# debug-header-feather.net
KiCad netlist of a schematic drawn in EAGLE
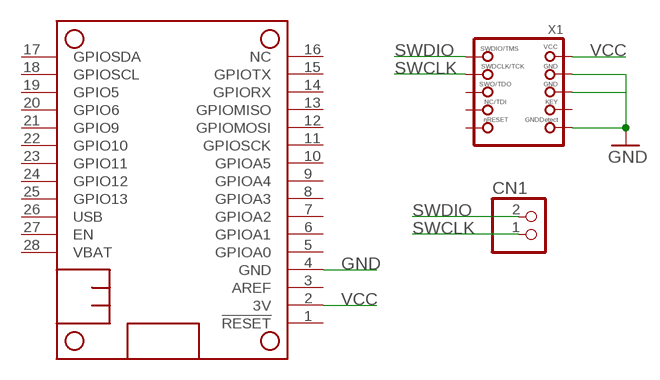
[diagram p0: schematic, sheet 1]

(export (version "E")
  (design (tool "Eeschema 10.0.6"))
  (components
    (comp (ref "CN1")
      (value "JST_2PIN-SMT-RA")
      (footprint "eagle-import:JST-PH-2-SMT-RA")
      (libsource (lib "eagle-import") (part "JST_2PIN-SMT-RA"))
    )
    (comp (ref "MS1")
      (value "FEATHERWING")
      (footprint "eagle-import:FEATHERWING")
      (libsource (lib "eagle-import") (part "FEATHERWING"))
    )
    (comp (ref "X1")
      (value "JTAG-CORTEX")
      (footprint "eagle-import:2X05_1.27MM_SMT")
      (libsource (lib "eagle-import") (part "JTAG-CORTEX"))
    )
  )
  (nets
    (net (code "1") (name "/SWCLK") (class "Default")
      (node (ref "CN1") (pin "1") (pinfunction "2_1") (pintype "passive"))
      (node (ref "X1") (pin "4") (pinfunction "SWDCLK_4") (pintype "bidirectional"))
    )
    (net (code "2") (name "/SWDIO") (class "Default")
      (node (ref "CN1") (pin "2") (pinfunction "1_2") (pintype "passive"))
      (node (ref "X1") (pin "2") (pinfunction "SWDIO_2") (pintype "bidirectional"))
    )
    (net (code "3") (name "/USB") (class "Default")
      (node (ref "MS1") (pin "26") (pinfunction "USB_26") (pintype "power_in"))
    )
    (net (code "4") (name "/VBAT") (class "Default")
      (node (ref "MS1") (pin "28") (pinfunction "VBAT_28") (pintype "power_in"))
    )
    (net (code "5") (name "/VCC") (class "Default")
      (node (ref "MS1") (pin "2") (pinfunction "3V_2") (pintype "power_in"))
      (node (ref "X1") (pin "1") (pinfunction "VCC_1") (pintype "power_in"))
    )
    (net (code "6") (name "GND") (class "Default")
      (node (ref "MS1") (pin "4") (pinfunction "GND_4") (pintype "power_in"))
      (node (ref "X1") (pin "3") (pinfunction "GND_3") (pintype "power_in"))
      (node (ref "X1") (pin "5") (pinfunction "GND_5") (pintype "power_in"))
      (node (ref "X1") (pin "9") (pinfunction "GNDDETECT_9") (pintype "bidirectional"))
    )
    (net (code "7") (name "unconnected-(MS1-AREF-Pad3)") (class "Default")
      (node (ref "MS1") (pin "3") (pinfunction "AREF_3") (pintype "passive"))
    )
    (net (code "8") (name "unconnected-(MS1-EN-Pad27)") (class "Default")
      (node (ref "MS1") (pin "27") (pinfunction "EN_27") (pintype "passive"))
    )
    (net (code "9") (name "unconnected-(MS1-GPIO5-Pad19)") (class "Default")
      (node (ref "MS1") (pin "19") (pinfunction "GPIO5_19") (pintype "bidirectional"))
    )
    (net (code "10") (name "unconnected-(MS1-GPIO6-Pad20)") (class "Default")
      (node (ref "MS1") (pin "20") (pinfunction "GPIO6_20") (pintype "bidirectional"))
    )
    (net (code "11") (name "unconnected-(MS1-GPIO9-Pad21)") (class "Default")
      (node (ref "MS1") (pin "21") (pinfunction "GPIO9_21") (pintype "bidirectional"))
    )
    (net (code "12") (name "unconnected-(MS1-GPIO10-Pad22)") (class "Default")
      (node (ref "MS1") (pin "22") (pinfunction "GPIO10_22") (pintype "bidirectional"))
    )
    (net (code "13") (name "unconnected-(MS1-GPIO11-Pad23)") (class "Default")
      (node (ref "MS1") (pin "23") (pinfunction "GPIO11_23") (pintype "bidirectional"))
    )
    (net (code "14") (name "unconnected-(MS1-GPIO12-Pad24)") (class "Default")
      (node (ref "MS1") (pin "24") (pinfunction "GPIO12_24") (pintype "bidirectional"))
    )
    (net (code "15") (name "unconnected-(MS1-GPIO13-Pad25)") (class "Default")
      (node (ref "MS1") (pin "25") (pinfunction "GPIO13_25") (pintype "bidirectional"))
    )
    (net (code "16") (name "unconnected-(MS1-GPIOA0-Pad5)") (class "Default")
      (node (ref "MS1") (pin "5") (pinfunction "GPIOA0_5") (pintype "bidirectional"))
    )
    (net (code "17") (name "unconnected-(MS1-GPIOA1-Pad6)") (class "Default")
      (node (ref "MS1") (pin "6") (pinfunction "GPIOA1_6") (pintype "bidirectional"))
    )
    (net (code "18") (name "unconnected-(MS1-GPIOA2-Pad7)") (class "Default")
      (node (ref "MS1") (pin "7") (pinfunction "GPIOA2_7") (pintype "bidirectional"))
    )
    (net (code "19") (name "unconnected-(MS1-GPIOA3-Pad8)") (class "Default")
      (node (ref "MS1") (pin "8") (pinfunction "GPIOA3_8") (pintype "bidirectional"))
    )
    (net (code "20") (name "unconnected-(MS1-GPIOA4-Pad9)") (class "Default")
      (node (ref "MS1") (pin "9") (pinfunction "GPIOA4_9") (pintype "bidirectional"))
    )
    (net (code "21") (name "unconnected-(MS1-GPIOA5-Pad10)") (class "Default")
      (node (ref "MS1") (pin "10") (pinfunction "GPIOA5_10") (pintype "bidirectional"))
    )
    (net (code "22") (name "unconnected-(MS1-GPIOMISO-Pad13)") (class "Default")
      (node (ref "MS1") (pin "13") (pinfunction "GPIOMISO_13") (pintype "bidirectional"))
    )
    (net (code "23") (name "unconnected-(MS1-GPIOMOSI-Pad12)") (class "Default")
      (node (ref "MS1") (pin "12") (pinfunction "GPIOMOSI_12") (pintype "bidirectional"))
    )
    (net (code "24") (name "unconnected-(MS1-GPIORX-Pad14)") (class "Default")
      (node (ref "MS1") (pin "14") (pinfunction "GPIORX_14") (pintype "bidirectional"))
    )
    (net (code "25") (name "unconnected-(MS1-GPIOSCK-Pad11)") (class "Default")
      (node (ref "MS1") (pin "11") (pinfunction "GPIOSCK_11") (pintype "bidirectional"))
    )
    (net (code "26") (name "unconnected-(MS1-GPIOSCL-Pad18)") (class "Default")
      (node (ref "MS1") (pin "18") (pinfunction "GPIOSCL_18") (pintype "bidirectional"))
    )
    (net (code "27") (name "unconnected-(MS1-GPIOSDA-Pad17)") (class "Default")
      (node (ref "MS1") (pin "17") (pinfunction "GPIOSDA_17") (pintype "bidirectional"))
    )
    (net (code "28") (name "unconnected-(MS1-GPIOTX-Pad15)") (class "Default")
      (node (ref "MS1") (pin "15") (pinfunction "GPIOTX_15") (pintype "bidirectional"))
    )
    (net (code "29") (name "unconnected-(MS1-NC-Pad16)") (class "Default")
      (node (ref "MS1") (pin "16") (pinfunction "NC_16") (pintype "passive"))
    )
    (net (code "30") (name "unconnected-(MS1-~{RESET}-Pad1)") (class "Default")
      (node (ref "MS1") (pin "1") (pinfunction "~{RESET}_1") (pintype "input"))
    )
    (net (code "31") (name "unconnected-(X1-KEY-Pad7)") (class "Default")
      (node (ref "X1") (pin "7") (pinfunction "KEY_7") (pintype "bidirectional"))
    )
    (net (code "32") (name "unconnected-(X1-NRESET-Pad10)") (class "Default")
      (node (ref "X1") (pin "10") (pinfunction "NRESET_10") (pintype "bidirectional"))
    )
    (net (code "33") (name "unconnected-(X1-SWO-Pad6)") (class "Default")
      (node (ref "X1") (pin "6") (pinfunction "SWO_6") (pintype "bidirectional"))
    )
    (net (code "34") (name "unconnected-(X1-TDI-Pad8)") (class "Default")
      (node (ref "X1") (pin "8") (pinfunction "TDI_8") (pintype "bidirectional"))
    )
  )
)
